# STK672-080.net
KiCad netlist of a schematic drawn in Altium Designer
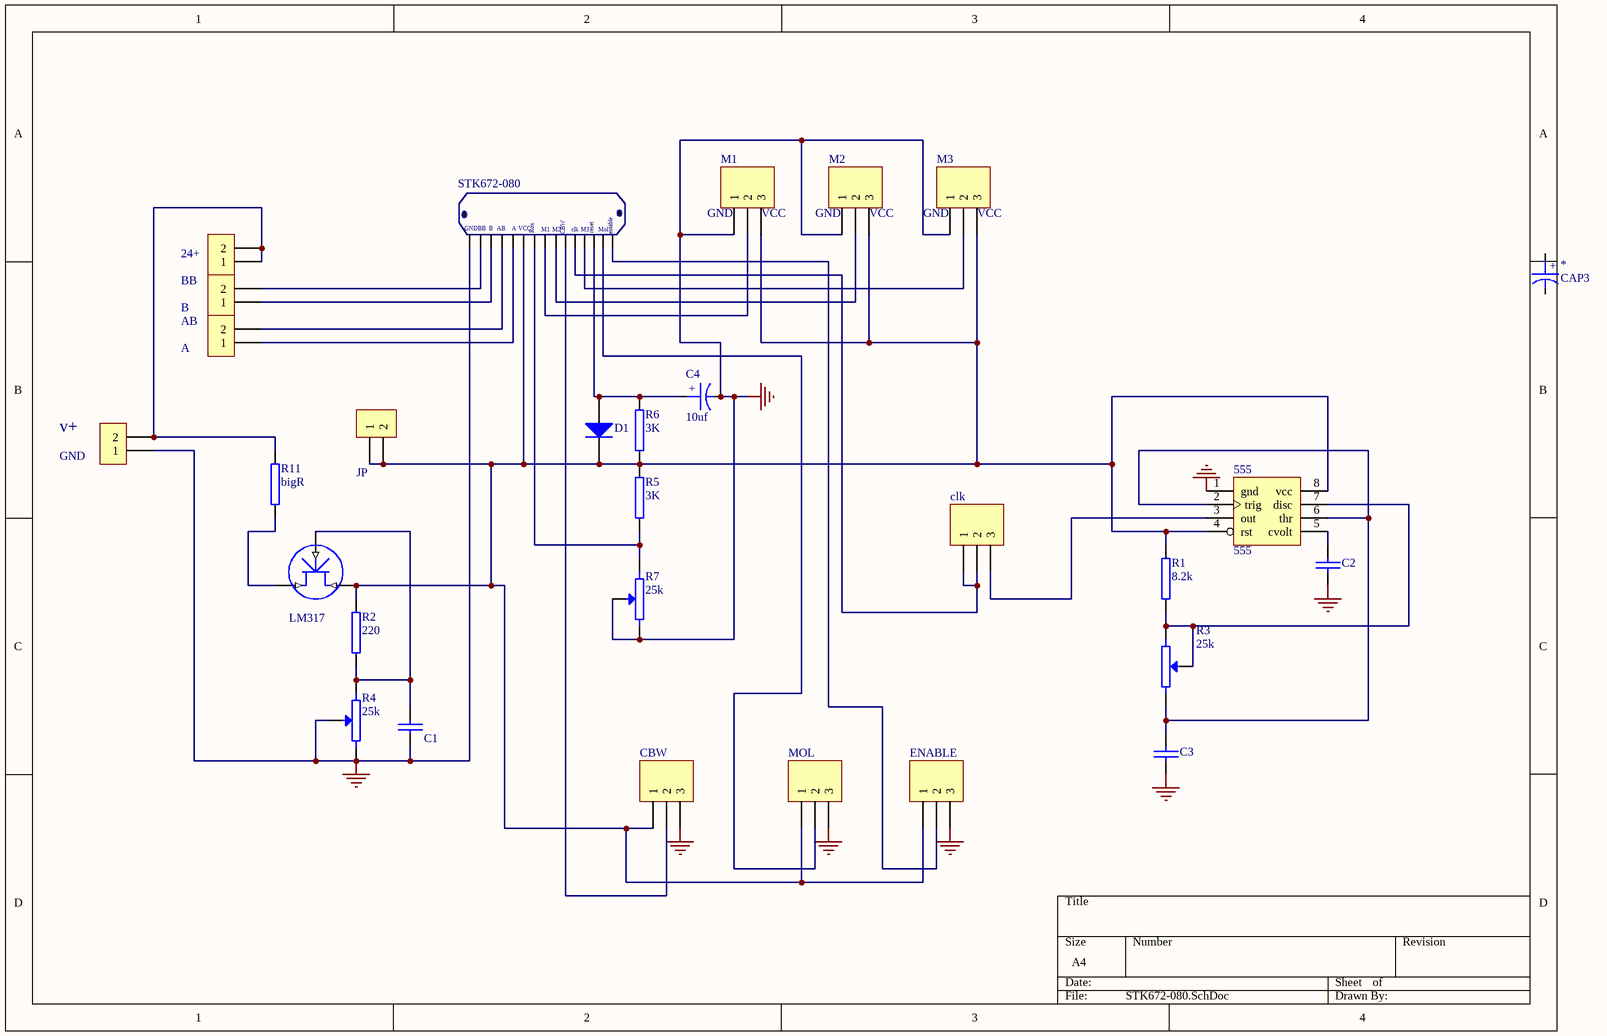
[diagram p0: STK672-080.SchDoc]

(export (version "E")
  (design (tool "Eeschema 10.0.6"))
  (components
    (comp (ref "*") (value "CAP3") (footprint "CAP3") (libsource (lib "OldCow1 (1)") (part "CAP3")))
    (comp (ref "24+") (value "POWER") (footprint "POWERPF") (libsource (lib "OldCow1 (1)") (part "POWER")))
    (comp (ref "555") (value "555") (footprint "DIP8") (libsource (lib "OldCow1 (1)") (part "555")))
    (comp (ref "C1")
      (value "15p")
      (footprint "RAD0.3")
      (description "Capacitor")
      (libsource (lib "OldCow1 (1)") (part "CAP"))
    )
    (comp (ref "C2")
      (value "15p")
      (footprint "RAD0.3")
      (description "Capacitor")
      (libsource (lib "OldCow1 (1)") (part "CAP"))
    )
    (comp (ref "C3")
      (value "15p")
      (footprint "RAD0.3")
      (description "Capacitor")
      (libsource (lib "OldCow1 (1)") (part "CAP"))
    )
    (comp (ref "C4")
      (value "10uf")
      (footprint "cap2")
      (description "Capacitor")
      (libsource (lib "OldCow1 (1)") (part "CAPACITOR POL"))
    )
    (comp (ref "CBW")
      (value "Header 3")
      (footprint "HDR1X3")
      (description "Header, 3-Pin")
      (fields (field (name "PUBLISHER") "Altium Limited"))
      (libsource (lib "Miscellaneous Connectors") (part "Header 3"))
    )
    (comp (ref "clk")
      (value "Header 3")
      (footprint "HDR1X3")
      (description "Header, 3-Pin")
      (fields (field (name "PUBLISHER") "Altium Limited"))
      (libsource (lib "Miscellaneous Connectors") (part "Header 3"))
    )
    (comp (ref "D1")
      (value "Diode 1N4007")
      (footprint "DO-41")
      (description "1 Amp General Purpose Rectifier")
      (fields (field (name "PUBLISHER") "Altium Limited"))
      (libsource (lib "Miscellaneous Devices") (part "Diode 1N4007"))
    )
    (comp (ref "ENABLE")
      (value "Header 3")
      (footprint "HDR1X3")
      (description "Header, 3-Pin")
      (fields (field (name "PUBLISHER") "Altium Limited"))
      (libsource (lib "Miscellaneous Connectors") (part "Header 3"))
    )
    (comp (ref "J2") (value "POWER") (footprint "POWERPF") (libsource (lib "OldCow1 (1)") (part "POWER")))
    (comp (ref "J3") (value "POWER") (footprint "POWERPF") (libsource (lib "OldCow1 (1)") (part "POWER")))
    (comp (ref "JP") (value "TESTPOINT") (footprint "tp") (libsource (lib "OldCow1 (1)") (part "TESTPOINT")))
    (comp (ref "LM317") (value "JFET N") (footprint "TO-221") (libsource (lib "OldCow1 (1)") (part "JFET N")))
    (comp (ref "M1")
      (value "Header 3")
      (footprint "HDR1X3")
      (description "Header, 3-Pin")
      (fields (field (name "PUBLISHER") "Altium Limited"))
      (libsource (lib "Miscellaneous Connectors") (part "Header 3"))
    )
    (comp (ref "M2")
      (value "Header 3")
      (footprint "HDR1X3")
      (description "Header, 3-Pin")
      (fields (field (name "PUBLISHER") "Altium Limited"))
      (libsource (lib "Miscellaneous Connectors") (part "Header 3"))
    )
    (comp (ref "M3")
      (value "Header 3")
      (footprint "HDR1X3")
      (description "Header, 3-Pin")
      (fields (field (name "PUBLISHER") "Altium Limited"))
      (libsource (lib "Miscellaneous Connectors") (part "Header 3"))
    )
    (comp (ref "MOL")
      (value "Header 3")
      (footprint "HDR1X3")
      (description "Header, 3-Pin")
      (fields (field (name "PUBLISHER") "Altium Limited"))
      (libsource (lib "Miscellaneous Connectors") (part "Header 3"))
    )
    (comp (ref "POWER") (value "POWER") (footprint "POWERPF") (libsource (lib "OldCow1 (1)") (part "POWER")))
    (comp (ref "R1") (value "8.2k") (footprint "AXIAL0.4") (libsource (lib "OldCow1 (1)") (part "RES2")))
    (comp (ref "R2") (value "220") (footprint "AXIAL0.4") (libsource (lib "OldCow1 (1)") (part "RES2")))
    (comp (ref "R3")
      (value "25k")
      (footprint "SIP3-D")
      (description "Potentiometer")
      (libsource (lib "OldCow1 (1)") (part "POT2"))
    )
    (comp (ref "R4")
      (value "25k")
      (footprint "SIP3-D")
      (description "Potentiometer")
      (libsource (lib "OldCow1 (1)") (part "POT2"))
    )
    (comp (ref "R5") (value "3K") (footprint "AXIAL0.4") (libsource (lib "OldCow1 (1)") (part "RES2")))
    (comp (ref "R6") (value "3K") (footprint "AXIAL0.4") (libsource (lib "OldCow1 (1)") (part "RES2")))
    (comp (ref "R7")
      (value "25k")
      (footprint "SIP3-D")
      (description "Potentiometer")
      (libsource (lib "OldCow1 (1)") (part "POT2"))
    )
    (comp (ref "R11") (value "bigR") (footprint "bigRPF") (libsource (lib "OldCow1 (1)") (part "bigR")))
    (comp (ref "STK672-080")
      (value "1")
      (footprint "STK672-080PF")
      (libsource (lib "OldCow1 (1)") (part "STK672-080"))
    )
  )
  (nets
    (net (code "1") (name "GND") (class "Default")
      (node (ref "555") (pin "1") (pinfunction "gnd_1") (pintype "passive"))
      (node (ref "C1") (pin "2") (pinfunction "2_2") (pintype "passive"))
      (node (ref "C2") (pin "2") (pinfunction "2_2") (pintype "passive"))
      (node (ref "C3") (pin "2") (pinfunction "2_2") (pintype "passive"))
      (node (ref "C4") (pin "2") (pinfunction "2_2") (pintype "passive"))
      (node (ref "CBW") (pin "3") (pinfunction "3_3") (pintype "passive"))
      (node (ref "ENABLE") (pin "3") (pinfunction "3_3") (pintype "passive"))
      (node (ref "M1") (pin "1") (pinfunction "1_1") (pintype "passive"))
      (node (ref "M2") (pin "1") (pinfunction "1_1") (pintype "passive"))
      (node (ref "M3") (pin "1") (pinfunction "1_1") (pintype "passive"))
      (node (ref "MOL") (pin "3") (pinfunction "3_3") (pintype "passive"))
      (node (ref "POWER") (pin "1") (pinfunction "1_1") (pintype "passive"))
      (node (ref "R4") (pin "1") (pinfunction "1_1") (pintype "passive"))
      (node (ref "R4") (pin "3") (pinfunction "W_3") (pintype "passive"))
      (node (ref "R7") (pin "1") (pinfunction "1_1") (pintype "passive"))
      (node (ref "R7") (pin "3") (pinfunction "W_3") (pintype "passive"))
      (node (ref "STK672-080") (pin "1") (pinfunction "VCC_1") (pintype "passive"))
    )
    (net (code "2") (name "Net-(24+-Pad1)") (class "Default")
      (node (ref "24+") (pin "1") (pinfunction "1_1") (pintype "passive"))
      (node (ref "24+") (pin "2") (pinfunction "2_2") (pintype "passive"))
      (node (ref "POWER") (pin "2") (pinfunction "2_2") (pintype "passive"))
      (node (ref "R11") (pin "2") (pinfunction "2_2") (pintype "passive"))
    )
    (net (code "3") (name "Net-(555-cvolt)") (class "Default")
      (node (ref "555") (pin "5") (pinfunction "cvolt_5") (pintype "passive"))
      (node (ref "C2") (pin "1") (pinfunction "1_1") (pintype "passive"))
    )
    (net (code "4") (name "Net-(555-disc)") (class "Default")
      (node (ref "555") (pin "7") (pinfunction "disc_7") (pintype "passive"))
      (node (ref "R1") (pin "1") (pinfunction "1_1") (pintype "passive"))
      (node (ref "R3") (pin "1") (pinfunction "1_1") (pintype "passive"))
      (node (ref "R3") (pin "3") (pinfunction "W_3") (pintype "passive"))
    )
    (net (code "5") (name "Net-(555-out)") (class "Default")
      (node (ref "555") (pin "3") (pinfunction "out_3") (pintype "passive"))
      (node (ref "clk") (pin "3") (pinfunction "3_3") (pintype "passive"))
    )
    (net (code "6") (name "Net-(555-rst)") (class "Default")
      (node (ref "555") (pin "4") (pinfunction "rst_4") (pintype "passive"))
      (node (ref "555") (pin "8") (pinfunction "vcc_8") (pintype "passive"))
      (node (ref "CBW") (pin "1") (pinfunction "1_1") (pintype "passive"))
      (node (ref "D1") (pin "2") (pinfunction "K_2") (pintype "passive"))
      (node (ref "ENABLE") (pin "1") (pinfunction "1_1") (pintype "passive"))
      (node (ref "JP") (pin "1") (pinfunction "1_1") (pintype "passive"))
      (node (ref "JP") (pin "2") (pinfunction "2_2") (pintype "passive"))
      (node (ref "LM317") (pin "2") (pinfunction "D_2") (pintype "input"))
      (node (ref "M1") (pin "3") (pinfunction "3_3") (pintype "passive"))
      (node (ref "M2") (pin "3") (pinfunction "3_3") (pintype "passive"))
      (node (ref "M3") (pin "3") (pinfunction "3_3") (pintype "passive"))
      (node (ref "MOL") (pin "1") (pinfunction "1_1") (pintype "passive"))
      (node (ref "R1") (pin "2") (pinfunction "2_2") (pintype "passive"))
      (node (ref "R2") (pin "2") (pinfunction "2_2") (pintype "passive"))
      (node (ref "R5") (pin "2") (pinfunction "2_2") (pintype "passive"))
      (node (ref "R6") (pin "1") (pinfunction "1_1") (pintype "passive"))
      (node (ref "STK672-080") (pin "6") (pinfunction "VCC_6") (pintype "passive"))
    )
    (net (code "7") (name "Net-(555-thr)") (class "Default")
      (node (ref "555") (pin "2") (pinfunction "trig_2") (pintype "passive"))
      (node (ref "555") (pin "6") (pinfunction "thr_6") (pintype "passive"))
      (node (ref "C3") (pin "1") (pinfunction "1_1") (pintype "passive"))
      (node (ref "R3") (pin "2") (pinfunction "2_2") (pintype "passive"))
    )
    (net (code "8") (name "Net-(D1-A)") (class "Default")
      (node (ref "C4") (pin "1") (pinfunction "1_1") (pintype "passive"))
      (node (ref "D1") (pin "1") (pinfunction "A_1") (pintype "passive"))
      (node (ref "R6") (pin "2") (pinfunction "2_2") (pintype "passive"))
      (node (ref "STK672-080") (pin "13") (pinfunction "RESET_13") (pintype "passive"))
    )
    (net (code "9") (name "Net-(ENABLE-Pad2)") (class "Default")
      (node (ref "ENABLE") (pin "2") (pinfunction "2_2") (pintype "passive"))
      (node (ref "STK672-080") (pin "15") (pinfunction "15_15") (pintype "passive"))
    )
    (net (code "10") (name "Net-(LM317-G)") (class "Default")
      (node (ref "C1") (pin "1") (pinfunction "1_1") (pintype "passive"))
      (node (ref "LM317") (pin "1") (pinfunction "G_1") (pintype "input"))
      (node (ref "R2") (pin "1") (pinfunction "1_1") (pintype "passive"))
      (node (ref "R4") (pin "2") (pinfunction "2_2") (pintype "passive"))
    )
    (net (code "11") (name "Net-(LM317-S)") (class "Default")
      (node (ref "LM317") (pin "3") (pinfunction "S_3") (pintype "input"))
      (node (ref "R11") (pin "1") (pinfunction "1_1") (pintype "passive"))
    )
    (net (code "12") (name "Net-(MOL-Pad2)") (class "Default")
      (node (ref "MOL") (pin "2") (pinfunction "2_2") (pintype "passive"))
      (node (ref "STK672-080") (pin "14") (pinfunction "14_14") (pintype "passive"))
    )
    (net (code "13") (name "Net-(STK672-080-A)") (class "Default")
      (node (ref "J3") (pin "1") (pinfunction "1_1") (pintype "passive"))
      (node (ref "STK672-080") (pin "5") (pinfunction "A_5") (pintype "passive"))
    )
    (net (code "14") (name "Net-(STK672-080-AB)") (class "Default")
      (node (ref "J3") (pin "2") (pinfunction "2_2") (pintype "passive"))
      (node (ref "STK672-080") (pin "4") (pinfunction "AB_4") (pintype "passive"))
    )
    (net (code "15") (name "Net-(STK672-080-B)") (class "Default")
      (node (ref "J2") (pin "1") (pinfunction "1_1") (pintype "passive"))
      (node (ref "STK672-080") (pin "3") (pinfunction "B_3") (pintype "passive"))
    )
    (net (code "16") (name "Net-(STK672-080-BB)") (class "Default")
      (node (ref "J2") (pin "2") (pinfunction "2_2") (pintype "passive"))
      (node (ref "STK672-080") (pin "2") (pinfunction "BB_2") (pintype "passive"))
    )
    (net (code "17") (name "Net-(STK672-080-CBW)") (class "Default")
      (node (ref "CBW") (pin "2") (pinfunction "2_2") (pintype "passive"))
      (node (ref "STK672-080") (pin "10") (pinfunction "CBW_10") (pintype "passive"))
    )
    (net (code "18") (name "Net-(STK672-080-CLK)") (class "Default")
      (node (ref "STK672-080") (pin "11") (pinfunction "CLK_11") (pintype "passive"))
      (node (ref "clk") (pin "1") (pinfunction "1_1") (pintype "passive"))
      (node (ref "clk") (pin "2") (pinfunction "2_2") (pintype "passive"))
    )
    (net (code "19") (name "Net-(STK672-080-M1)") (class "Default")
      (node (ref "M1") (pin "2") (pinfunction "2_2") (pintype "passive"))
      (node (ref "STK672-080") (pin "8") (pinfunction "M1_8") (pintype "passive"))
    )
    (net (code "20") (name "Net-(STK672-080-M2)") (class "Default")
      (node (ref "M2") (pin "2") (pinfunction "2_2") (pintype "passive"))
      (node (ref "STK672-080") (pin "9") (pinfunction "M2_9") (pintype "passive"))
    )
    (net (code "21") (name "Net-(STK672-080-M3)") (class "Default")
      (node (ref "M3") (pin "2") (pinfunction "2_2") (pintype "passive"))
      (node (ref "STK672-080") (pin "12") (pinfunction "M3_12") (pintype "passive"))
    )
    (net (code "22") (name "Net-(STK672-080-Rox)") (class "Default")
      (node (ref "R5") (pin "1") (pinfunction "1_1") (pintype "passive"))
      (node (ref "R7") (pin "2") (pinfunction "2_2") (pintype "passive"))
      (node (ref "STK672-080") (pin "7") (pinfunction "Rox_7") (pintype "passive"))
    )
    (net (code "23") (name "unconnected-(*-Pad1)") (class "Default")
      (node (ref "*") (pin "1") (pinfunction "1_1") (pintype "passive"))
    )
    (net (code "24") (name "unconnected-(*-Pad2)") (class "Default")
      (node (ref "*") (pin "2") (pinfunction "2_2") (pintype "passive"))
    )
  )
)
